# led80tiny85.net
KiCad netlist of a schematic drawn in EAGLE
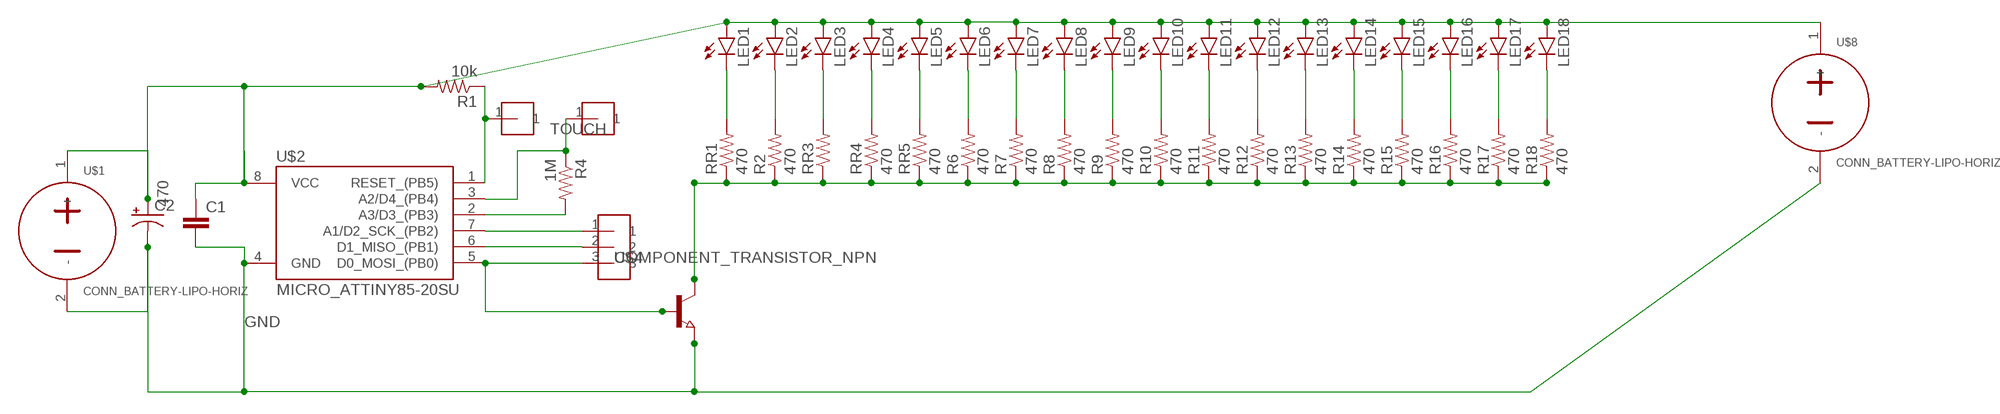
[diagram p0: schematic, sheet 1]

(export (version "E")
  (design (tool "Eeschema 10.0.6"))
  (components
    (comp (ref "C1")
      (value "COMPONENT_CAP-0805")
      (footprint "eagle-import:0805")
      (libsource (lib "eagle-import") (part "COMPONENT_CAP-0805"))
    )
    (comp (ref "C2")
      (value "COMPONENT_CAP_POL-8MM")
      (footprint "eagle-import:CAP_RADIAL_CAN_6.3MM")
      (libsource (lib "eagle-import") (part "COMPONENT_CAP_POL-8MM"))
    )
    (comp (ref "LED1")
      (value "LED-0805")
      (footprint "eagle-import:CHIP-LED0805")
      (libsource (lib "eagle-import") (part "LED-0805"))
    )
    (comp (ref "LED2")
      (value "LED-0805")
      (footprint "eagle-import:CHIP-LED0805")
      (libsource (lib "eagle-import") (part "LED-0805"))
    )
    (comp (ref "LED3")
      (value "LED-0805")
      (footprint "eagle-import:CHIP-LED0805")
      (libsource (lib "eagle-import") (part "LED-0805"))
    )
    (comp (ref "LED4")
      (value "LED-0805")
      (footprint "eagle-import:CHIP-LED0805")
      (libsource (lib "eagle-import") (part "LED-0805"))
    )
    (comp (ref "LED5")
      (value "LED-0805")
      (footprint "eagle-import:CHIP-LED0805")
      (libsource (lib "eagle-import") (part "LED-0805"))
    )
    (comp (ref "LED6")
      (value "LED-0805")
      (footprint "eagle-import:CHIP-LED0805")
      (libsource (lib "eagle-import") (part "LED-0805"))
    )
    (comp (ref "LED7")
      (value "LED-0805")
      (footprint "eagle-import:CHIP-LED0805")
      (libsource (lib "eagle-import") (part "LED-0805"))
    )
    (comp (ref "LED8")
      (value "LED-0805")
      (footprint "eagle-import:CHIP-LED0805")
      (libsource (lib "eagle-import") (part "LED-0805"))
    )
    (comp (ref "LED9")
      (value "LED-0805")
      (footprint "eagle-import:CHIP-LED0805")
      (libsource (lib "eagle-import") (part "LED-0805"))
    )
    (comp (ref "LED10")
      (value "LED-0805")
      (footprint "eagle-import:CHIP-LED0805")
      (libsource (lib "eagle-import") (part "LED-0805"))
    )
    (comp (ref "LED11")
      (value "LED-0805")
      (footprint "eagle-import:CHIP-LED0805")
      (libsource (lib "eagle-import") (part "LED-0805"))
    )
    (comp (ref "LED12")
      (value "LED-0805")
      (footprint "eagle-import:CHIP-LED0805")
      (libsource (lib "eagle-import") (part "LED-0805"))
    )
    (comp (ref "LED13")
      (value "LED-0805")
      (footprint "eagle-import:CHIP-LED0805")
      (libsource (lib "eagle-import") (part "LED-0805"))
    )
    (comp (ref "LED14")
      (value "LED-0805")
      (footprint "eagle-import:CHIP-LED0805")
      (libsource (lib "eagle-import") (part "LED-0805"))
    )
    (comp (ref "LED15")
      (value "LED-0805")
      (footprint "eagle-import:CHIP-LED0805")
      (libsource (lib "eagle-import") (part "LED-0805"))
    )
    (comp (ref "LED16")
      (value "LED-0805")
      (footprint "eagle-import:CHIP-LED0805")
      (libsource (lib "eagle-import") (part "LED-0805"))
    )
    (comp (ref "LED17")
      (value "LED-0805")
      (footprint "eagle-import:CHIP-LED0805")
      (libsource (lib "eagle-import") (part "LED-0805"))
    )
    (comp (ref "LED18")
      (value "LED-0805")
      (footprint "eagle-import:CHIP-LED0805")
      (libsource (lib "eagle-import") (part "LED-0805"))
    )
    (comp (ref "R1")
      (value "10k")
      (footprint "eagle-import:0805")
      (libsource (lib "eagle-import") (part "COMPONENT_RESISTOR-0805"))
    )
    (comp (ref "R2")
      (value "470")
      (footprint "eagle-import:0805")
      (libsource (lib "eagle-import") (part "COMPONENT_RESISTOR-0805"))
    )
    (comp (ref "R4")
      (value "1M")
      (footprint "eagle-import:0805")
      (libsource (lib "eagle-import") (part "COMPONENT_RESISTOR-0805"))
    )
    (comp (ref "R6")
      (value "470")
      (footprint "eagle-import:0805")
      (libsource (lib "eagle-import") (part "COMPONENT_RESISTOR-0805"))
    )
    (comp (ref "R7")
      (value "470")
      (footprint "eagle-import:0805")
      (libsource (lib "eagle-import") (part "COMPONENT_RESISTOR-0805"))
    )
    (comp (ref "R8")
      (value "470")
      (footprint "eagle-import:0805")
      (libsource (lib "eagle-import") (part "COMPONENT_RESISTOR-0805"))
    )
    (comp (ref "R9")
      (value "470")
      (footprint "eagle-import:0805")
      (libsource (lib "eagle-import") (part "COMPONENT_RESISTOR-0805"))
    )
    (comp (ref "R10")
      (value "470")
      (footprint "eagle-import:0805")
      (libsource (lib "eagle-import") (part "COMPONENT_RESISTOR-0805"))
    )
    (comp (ref "R11")
      (value "470")
      (footprint "eagle-import:0805")
      (libsource (lib "eagle-import") (part "COMPONENT_RESISTOR-0805"))
    )
    (comp (ref "R12")
      (value "470")
      (footprint "eagle-import:0805")
      (libsource (lib "eagle-import") (part "COMPONENT_RESISTOR-0805"))
    )
    (comp (ref "R13")
      (value "470")
      (footprint "eagle-import:0805")
      (libsource (lib "eagle-import") (part "COMPONENT_RESISTOR-0805"))
    )
    (comp (ref "R14")
      (value "470")
      (footprint "eagle-import:0805")
      (libsource (lib "eagle-import") (part "COMPONENT_RESISTOR-0805"))
    )
    (comp (ref "R15")
      (value "470")
      (footprint "eagle-import:0805")
      (libsource (lib "eagle-import") (part "COMPONENT_RESISTOR-0805"))
    )
    (comp (ref "R16")
      (value "470")
      (footprint "eagle-import:0805")
      (libsource (lib "eagle-import") (part "COMPONENT_RESISTOR-0805"))
    )
    (comp (ref "R17")
      (value "470")
      (footprint "eagle-import:0805")
      (libsource (lib "eagle-import") (part "COMPONENT_RESISTOR-0805"))
    )
    (comp (ref "R18")
      (value "470")
      (footprint "eagle-import:0805")
      (libsource (lib "eagle-import") (part "COMPONENT_RESISTOR-0805"))
    )
    (comp (ref "RR1")
      (value "470")
      (footprint "eagle-import:0805")
      (libsource (lib "eagle-import") (part "COMPONENT_RESISTOR-0805"))
    )
    (comp (ref "RR3")
      (value "470")
      (footprint "eagle-import:0805")
      (libsource (lib "eagle-import") (part "COMPONENT_RESISTOR-0805"))
    )
    (comp (ref "RR4")
      (value "470")
      (footprint "eagle-import:0805")
      (libsource (lib "eagle-import") (part "COMPONENT_RESISTOR-0805"))
    )
    (comp (ref "RR5")
      (value "470")
      (footprint "eagle-import:0805")
      (libsource (lib "eagle-import") (part "COMPONENT_RESISTOR-0805"))
    )
    (comp (ref "U$1")
      (value "CONN_BATTERY-LIPO-HORIZ")
      (footprint "eagle-import:JST-PH-2-SMT-RA")
      (libsource (lib "eagle-import") (part "CONN_BATTERY-LIPO-HORIZ"))
    )
    (comp (ref "U$2")
      (value "MICRO_ATTINY85-20SU")
      (footprint "eagle-import:SOIC8")
      (libsource (lib "eagle-import") (part "MICRO_ATTINY85-20SU"))
    )
    (comp (ref "U$4")
      (value "COMPONENT_TRANSISTOR_NPN")
      (footprint "eagle-import:SOT23")
      (libsource (lib "eagle-import") (part "COMPONENT_TRANSISTOR_NPN"))
    )
    (comp (ref "U$5")
      (value "HEADER-1-TESTPOINT")
      (footprint "eagle-import:TESTPOINT-1")
      (libsource (lib "eagle-import") (part "HEADER-1-TESTPOINT"))
    )
    (comp (ref "U$6")
      (value "HEADER-1-TESTPOINT")
      (footprint "eagle-import:TESTPOINT-1")
      (libsource (lib "eagle-import") (part "HEADER-1-TESTPOINT"))
    )
    (comp (ref "U$7")
      (value "HEADER-3-TESTPOINT")
      (footprint "eagle-import:TESTPOINT-3")
      (libsource (lib "eagle-import") (part "HEADER-3-TESTPOINT"))
    )
    (comp (ref "U$8")
      (value "CONN_BATTERY-LIPO-HORIZ")
      (footprint "eagle-import:JST-PH-2-SMT-RA")
      (libsource (lib "eagle-import") (part "CONN_BATTERY-LIPO-HORIZ"))
    )
  )
  (nets
    (net (code "1") (name "/GND") (class "Default")
      (node (ref "C1") (pin "2") (pinfunction "2_2") (pintype "passive"))
      (node (ref "C2") (pin "-") (pinfunction "-_-") (pintype "passive"))
      (node (ref "U$1") (pin "2") (pinfunction "-_2") (pintype "bidirectional"))
      (node (ref "U$2") (pin "4") (pinfunction "GND_4") (pintype "power_in"))
      (node (ref "U$4") (pin "2") (pinfunction "E_2") (pintype "passive"))
      (node (ref "U$8") (pin "2") (pinfunction "-_2") (pintype "bidirectional"))
    )
    (net (code "2") (name "/TOUCH") (class "Default")
      (node (ref "R4") (pin "1") (pinfunction "1_1") (pintype "passive"))
      (node (ref "U$2") (pin "3") (pinfunction "A2/D4_(PB4)_3") (pintype "bidirectional"))
      (node (ref "U$5") (pin "1") (pinfunction "1_1") (pintype "bidirectional"))
    )
    (net (code "3") (name "Net-(LED1-PadC)") (class "Default")
      (node (ref "LED1") (pin "C") (pinfunction "C_C") (pintype "passive"))
      (node (ref "RR1") (pin "2") (pinfunction "2_2") (pintype "passive"))
    )
    (net (code "4") (name "Net-(LED2-PadC)") (class "Default")
      (node (ref "LED2") (pin "C") (pinfunction "C_C") (pintype "passive"))
      (node (ref "R2") (pin "2") (pinfunction "2_2") (pintype "passive"))
    )
    (net (code "5") (name "Net-(LED3-PadC)") (class "Default")
      (node (ref "LED3") (pin "C") (pinfunction "C_C") (pintype "passive"))
      (node (ref "RR3") (pin "2") (pinfunction "2_2") (pintype "passive"))
    )
    (net (code "6") (name "Net-(LED4-PadC)") (class "Default")
      (node (ref "LED4") (pin "C") (pinfunction "C_C") (pintype "passive"))
      (node (ref "RR4") (pin "2") (pinfunction "2_2") (pintype "passive"))
    )
    (net (code "7") (name "Net-(LED5-PadC)") (class "Default")
      (node (ref "LED5") (pin "C") (pinfunction "C_C") (pintype "passive"))
      (node (ref "RR5") (pin "2") (pinfunction "2_2") (pintype "passive"))
    )
    (net (code "8") (name "Net-(LED6-PadC)") (class "Default")
      (node (ref "LED6") (pin "C") (pinfunction "C_C") (pintype "passive"))
      (node (ref "R6") (pin "2") (pinfunction "2_2") (pintype "passive"))
    )
    (net (code "9") (name "Net-(LED7-PadC)") (class "Default")
      (node (ref "LED7") (pin "C") (pinfunction "C_C") (pintype "passive"))
      (node (ref "R7") (pin "2") (pinfunction "2_2") (pintype "passive"))
    )
    (net (code "10") (name "Net-(LED8-PadC)") (class "Default")
      (node (ref "LED8") (pin "C") (pinfunction "C_C") (pintype "passive"))
      (node (ref "R8") (pin "2") (pinfunction "2_2") (pintype "passive"))
    )
    (net (code "11") (name "Net-(LED9-PadC)") (class "Default")
      (node (ref "LED9") (pin "C") (pinfunction "C_C") (pintype "passive"))
      (node (ref "R9") (pin "2") (pinfunction "2_2") (pintype "passive"))
    )
    (net (code "12") (name "Net-(LED10-PadC)") (class "Default")
      (node (ref "LED10") (pin "C") (pinfunction "C_C") (pintype "passive"))
      (node (ref "R10") (pin "2") (pinfunction "2_2") (pintype "passive"))
    )
    (net (code "13") (name "Net-(LED11-PadC)") (class "Default")
      (node (ref "LED11") (pin "C") (pinfunction "C_C") (pintype "passive"))
      (node (ref "R11") (pin "2") (pinfunction "2_2") (pintype "passive"))
    )
    (net (code "14") (name "Net-(LED12-PadC)") (class "Default")
      (node (ref "LED12") (pin "C") (pinfunction "C_C") (pintype "passive"))
      (node (ref "R12") (pin "2") (pinfunction "2_2") (pintype "passive"))
    )
    (net (code "15") (name "Net-(LED13-PadC)") (class "Default")
      (node (ref "LED13") (pin "C") (pinfunction "C_C") (pintype "passive"))
      (node (ref "R13") (pin "2") (pinfunction "2_2") (pintype "passive"))
    )
    (net (code "16") (name "Net-(LED14-PadC)") (class "Default")
      (node (ref "LED14") (pin "C") (pinfunction "C_C") (pintype "passive"))
      (node (ref "R14") (pin "2") (pinfunction "2_2") (pintype "passive"))
    )
    (net (code "17") (name "Net-(LED15-PadC)") (class "Default")
      (node (ref "LED15") (pin "C") (pinfunction "C_C") (pintype "passive"))
      (node (ref "R15") (pin "2") (pinfunction "2_2") (pintype "passive"))
    )
    (net (code "18") (name "Net-(LED16-PadC)") (class "Default")
      (node (ref "LED16") (pin "C") (pinfunction "C_C") (pintype "passive"))
      (node (ref "R16") (pin "2") (pinfunction "2_2") (pintype "passive"))
    )
    (net (code "19") (name "Net-(LED17-PadC)") (class "Default")
      (node (ref "LED17") (pin "C") (pinfunction "C_C") (pintype "passive"))
      (node (ref "R17") (pin "2") (pinfunction "2_2") (pintype "passive"))
    )
    (net (code "20") (name "Net-(LED18-PadC)") (class "Default")
      (node (ref "LED18") (pin "C") (pinfunction "C_C") (pintype "passive"))
      (node (ref "R18") (pin "2") (pinfunction "2_2") (pintype "passive"))
    )
    (net (code "21") (name "Net-(U$1-+)") (class "Default")
      (node (ref "C1") (pin "1") (pinfunction "1_1") (pintype "passive"))
      (node (ref "C2") (pin "+") (pinfunction "+_+") (pintype "passive"))
      (node (ref "LED1") (pin "A") (pinfunction "A_A") (pintype "passive"))
      (node (ref "LED10") (pin "A") (pinfunction "A_A") (pintype "passive"))
      (node (ref "LED11") (pin "A") (pinfunction "A_A") (pintype "passive"))
      (node (ref "LED12") (pin "A") (pinfunction "A_A") (pintype "passive"))
      (node (ref "LED13") (pin "A") (pinfunction "A_A") (pintype "passive"))
      (node (ref "LED14") (pin "A") (pinfunction "A_A") (pintype "passive"))
      (node (ref "LED15") (pin "A") (pinfunction "A_A") (pintype "passive"))
      (node (ref "LED16") (pin "A") (pinfunction "A_A") (pintype "passive"))
      (node (ref "LED17") (pin "A") (pinfunction "A_A") (pintype "passive"))
      (node (ref "LED18") (pin "A") (pinfunction "A_A") (pintype "passive"))
      (node (ref "LED2") (pin "A") (pinfunction "A_A") (pintype "passive"))
      (node (ref "LED3") (pin "A") (pinfunction "A_A") (pintype "passive"))
      (node (ref "LED4") (pin "A") (pinfunction "A_A") (pintype "passive"))
      (node (ref "LED5") (pin "A") (pinfunction "A_A") (pintype "passive"))
      (node (ref "LED6") (pin "A") (pinfunction "A_A") (pintype "passive"))
      (node (ref "LED7") (pin "A") (pinfunction "A_A") (pintype "passive"))
      (node (ref "LED8") (pin "A") (pinfunction "A_A") (pintype "passive"))
      (node (ref "LED9") (pin "A") (pinfunction "A_A") (pintype "passive"))
      (node (ref "R1") (pin "2") (pinfunction "2_2") (pintype "passive"))
      (node (ref "U$1") (pin "1") (pinfunction "+_1") (pintype "bidirectional"))
      (node (ref "U$2") (pin "8") (pinfunction "VCC_8") (pintype "power_in"))
      (node (ref "U$8") (pin "1") (pinfunction "+_1") (pintype "bidirectional"))
    )
    (net (code "22") (name "Net-(U$2-A1{slash}D2_SCK_(PB2))") (class "Default")
      (node (ref "U$2") (pin "7") (pinfunction "A1/D2_SCK_(PB2)_7") (pintype "bidirectional"))
      (node (ref "U$7") (pin "1") (pinfunction "1_1") (pintype "bidirectional"))
    )
    (net (code "23") (name "Net-(U$2-A3{slash}D3_(PB3))") (class "Default")
      (node (ref "R4") (pin "2") (pinfunction "2_2") (pintype "passive"))
      (node (ref "U$2") (pin "2") (pinfunction "A3/D3_(PB3)_2") (pintype "bidirectional"))
    )
    (net (code "24") (name "Net-(U$2-D0_MOSI_(PB0))") (class "Default")
      (node (ref "U$2") (pin "5") (pinfunction "D0_MOSI_(PB0)_5") (pintype "bidirectional"))
      (node (ref "U$4") (pin "1") (pinfunction "B_1") (pintype "passive"))
      (node (ref "U$7") (pin "3") (pinfunction "3_3") (pintype "bidirectional"))
    )
    (net (code "25") (name "Net-(U$2-D1_MISO_(PB1))") (class "Default")
      (node (ref "U$2") (pin "6") (pinfunction "D1_MISO_(PB1)_6") (pintype "bidirectional"))
      (node (ref "U$7") (pin "2") (pinfunction "2_2") (pintype "bidirectional"))
    )
    (net (code "26") (name "Net-(U$2-RESET_(PB5))") (class "Default")
      (node (ref "R1") (pin "1") (pinfunction "1_1") (pintype "passive"))
      (node (ref "U$2") (pin "1") (pinfunction "RESET_(PB5)_1") (pintype "bidirectional"))
      (node (ref "U$6") (pin "1") (pinfunction "1_1") (pintype "bidirectional"))
    )
    (net (code "27") (name "Net-(U$4-C)") (class "Default")
      (node (ref "R10") (pin "1") (pinfunction "1_1") (pintype "passive"))
      (node (ref "R11") (pin "1") (pinfunction "1_1") (pintype "passive"))
      (node (ref "R12") (pin "1") (pinfunction "1_1") (pintype "passive"))
      (node (ref "R13") (pin "1") (pinfunction "1_1") (pintype "passive"))
      (node (ref "R14") (pin "1") (pinfunction "1_1") (pintype "passive"))
      (node (ref "R15") (pin "1") (pinfunction "1_1") (pintype "passive"))
      (node (ref "R16") (pin "1") (pinfunction "1_1") (pintype "passive"))
      (node (ref "R17") (pin "1") (pinfunction "1_1") (pintype "passive"))
      (node (ref "R18") (pin "1") (pinfunction "1_1") (pintype "passive"))
      (node (ref "R2") (pin "1") (pinfunction "1_1") (pintype "passive"))
      (node (ref "R6") (pin "1") (pinfunction "1_1") (pintype "passive"))
      (node (ref "R7") (pin "1") (pinfunction "1_1") (pintype "passive"))
      (node (ref "R8") (pin "1") (pinfunction "1_1") (pintype "passive"))
      (node (ref "R9") (pin "1") (pinfunction "1_1") (pintype "passive"))
      (node (ref "RR1") (pin "1") (pinfunction "1_1") (pintype "passive"))
      (node (ref "RR3") (pin "1") (pinfunction "1_1") (pintype "passive"))
      (node (ref "RR4") (pin "1") (pinfunction "1_1") (pintype "passive"))
      (node (ref "RR5") (pin "1") (pinfunction "1_1") (pintype "passive"))
      (node (ref "U$4") (pin "3") (pinfunction "C_3") (pintype "passive"))
    )
  )
)
